# main.net
KiCad netlist of a schematic drawn in Altium Designer
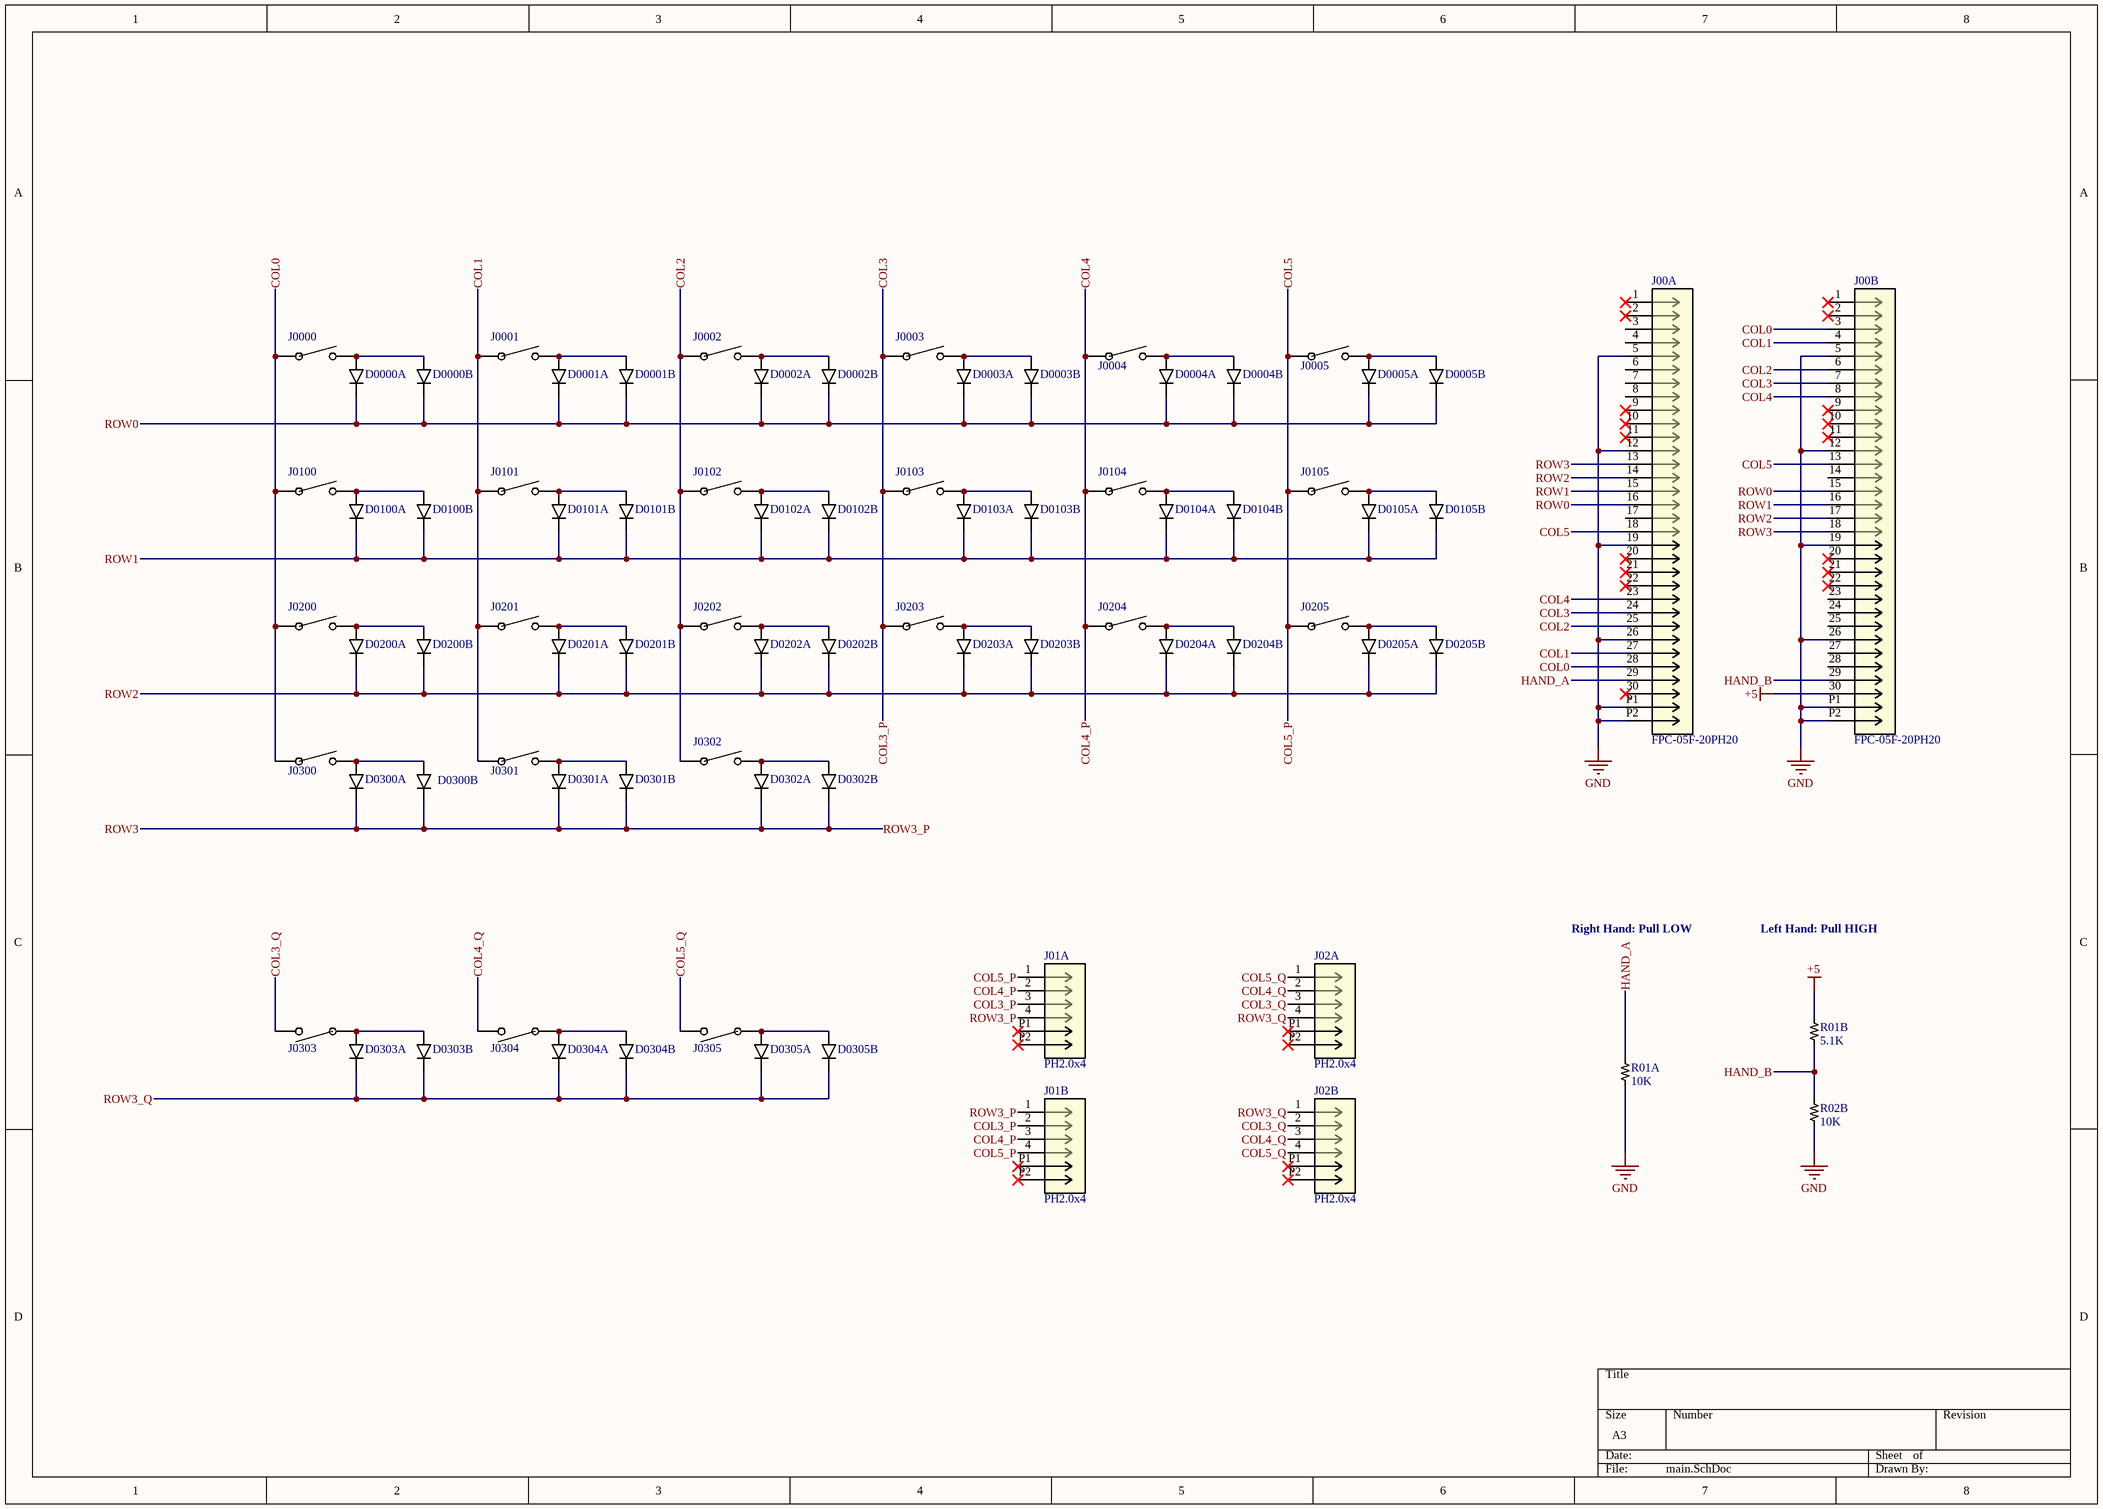
[diagram p0: main.SchDoc]

(export (version "E")
  (design (tool "Eeschema 10.0.6"))
  (components
    (comp (ref "D0000A")
      (value "1N4148W")
      (footprint "SOD123_DIO")
      (description "Small Signal Diode")
      (libsource (lib "Cornix_Library") (part "1N4148W"))
    )
    (comp (ref "D0000B")
      (value "1N4148W")
      (footprint "SOD123_DIO")
      (description "Small Signal Diode")
      (libsource (lib "Cornix_Library") (part "1N4148W"))
    )
    (comp (ref "D0001A")
      (value "1N4148W")
      (footprint "SOD123_DIO")
      (description "Small Signal Diode")
      (libsource (lib "Cornix_Library") (part "1N4148W"))
    )
    (comp (ref "D0001B")
      (value "1N4148W")
      (footprint "SOD123_DIO")
      (description "Small Signal Diode")
      (libsource (lib "Cornix_Library") (part "1N4148W"))
    )
    (comp (ref "D0002A")
      (value "1N4148W")
      (footprint "SOD123_DIO")
      (description "Small Signal Diode")
      (libsource (lib "Cornix_Library") (part "1N4148W"))
    )
    (comp (ref "D0002B")
      (value "1N4148W")
      (footprint "SOD123_DIO")
      (description "Small Signal Diode")
      (libsource (lib "Cornix_Library") (part "1N4148W"))
    )
    (comp (ref "D0003A")
      (value "1N4148W")
      (footprint "SOD123_DIO")
      (description "Small Signal Diode")
      (libsource (lib "Cornix_Library") (part "1N4148W"))
    )
    (comp (ref "D0003B")
      (value "1N4148W")
      (footprint "SOD123_DIO")
      (description "Small Signal Diode")
      (libsource (lib "Cornix_Library") (part "1N4148W"))
    )
    (comp (ref "D0004A")
      (value "1N4148W")
      (footprint "SOD123_DIO")
      (description "Small Signal Diode")
      (libsource (lib "Cornix_Library") (part "1N4148W"))
    )
    (comp (ref "D0004B")
      (value "1N4148W")
      (footprint "SOD123_DIO")
      (description "Small Signal Diode")
      (libsource (lib "Cornix_Library") (part "1N4148W"))
    )
    (comp (ref "D0005A")
      (value "1N4148W")
      (footprint "SOD123_DIO")
      (description "Small Signal Diode")
      (libsource (lib "Cornix_Library") (part "1N4148W"))
    )
    (comp (ref "D0005B")
      (value "1N4148W")
      (footprint "SOD123_DIO")
      (description "Small Signal Diode")
      (libsource (lib "Cornix_Library") (part "1N4148W"))
    )
    (comp (ref "D0100A")
      (value "1N4148W")
      (footprint "SOD123_DIO")
      (description "Small Signal Diode")
      (libsource (lib "Cornix_Library") (part "1N4148W"))
    )
    (comp (ref "D0100B")
      (value "1N4148W")
      (footprint "SOD123_DIO")
      (description "Small Signal Diode")
      (libsource (lib "Cornix_Library") (part "1N4148W"))
    )
    (comp (ref "D0101A")
      (value "1N4148W")
      (footprint "SOD123_DIO")
      (description "Small Signal Diode")
      (libsource (lib "Cornix_Library") (part "1N4148W"))
    )
    (comp (ref "D0101B")
      (value "1N4148W")
      (footprint "SOD123_DIO")
      (description "Small Signal Diode")
      (libsource (lib "Cornix_Library") (part "1N4148W"))
    )
    (comp (ref "D0102A")
      (value "1N4148W")
      (footprint "SOD123_DIO")
      (description "Small Signal Diode")
      (libsource (lib "Cornix_Library") (part "1N4148W"))
    )
    (comp (ref "D0102B")
      (value "1N4148W")
      (footprint "SOD123_DIO")
      (description "Small Signal Diode")
      (libsource (lib "Cornix_Library") (part "1N4148W"))
    )
    (comp (ref "D0103A")
      (value "1N4148W")
      (footprint "SOD123_DIO")
      (description "Small Signal Diode")
      (libsource (lib "Cornix_Library") (part "1N4148W"))
    )
    (comp (ref "D0103B")
      (value "1N4148W")
      (footprint "SOD123_DIO")
      (description "Small Signal Diode")
      (libsource (lib "Cornix_Library") (part "1N4148W"))
    )
    (comp (ref "D0104A")
      (value "1N4148W")
      (footprint "SOD123_DIO")
      (description "Small Signal Diode")
      (libsource (lib "Cornix_Library") (part "1N4148W"))
    )
    (comp (ref "D0104B")
      (value "1N4148W")
      (footprint "SOD123_DIO")
      (description "Small Signal Diode")
      (libsource (lib "Cornix_Library") (part "1N4148W"))
    )
    (comp (ref "D0105A")
      (value "1N4148W")
      (footprint "SOD123_DIO")
      (description "Small Signal Diode")
      (libsource (lib "Cornix_Library") (part "1N4148W"))
    )
    (comp (ref "D0105B")
      (value "1N4148W")
      (footprint "SOD123_DIO")
      (description "Small Signal Diode")
      (libsource (lib "Cornix_Library") (part "1N4148W"))
    )
    (comp (ref "D0200A")
      (value "1N4148W")
      (footprint "SOD123_DIO")
      (description "Small Signal Diode")
      (libsource (lib "Cornix_Library") (part "1N4148W"))
    )
    (comp (ref "D0200B")
      (value "1N4148W")
      (footprint "SOD123_DIO")
      (description "Small Signal Diode")
      (libsource (lib "Cornix_Library") (part "1N4148W"))
    )
    (comp (ref "D0201A")
      (value "1N4148W")
      (footprint "SOD123_DIO")
      (description "Small Signal Diode")
      (libsource (lib "Cornix_Library") (part "1N4148W"))
    )
    (comp (ref "D0201B")
      (value "1N4148W")
      (footprint "SOD123_DIO")
      (description "Small Signal Diode")
      (libsource (lib "Cornix_Library") (part "1N4148W"))
    )
    (comp (ref "D0202A")
      (value "1N4148W")
      (footprint "SOD123_DIO")
      (description "Small Signal Diode")
      (libsource (lib "Cornix_Library") (part "1N4148W"))
    )
    (comp (ref "D0202B")
      (value "1N4148W")
      (footprint "SOD123_DIO")
      (description "Small Signal Diode")
      (libsource (lib "Cornix_Library") (part "1N4148W"))
    )
    (comp (ref "D0203A")
      (value "1N4148W")
      (footprint "SOD123_DIO")
      (description "Small Signal Diode")
      (libsource (lib "Cornix_Library") (part "1N4148W"))
    )
    (comp (ref "D0203B")
      (value "1N4148W")
      (footprint "SOD123_DIO")
      (description "Small Signal Diode")
      (libsource (lib "Cornix_Library") (part "1N4148W"))
    )
    (comp (ref "D0204A")
      (value "1N4148W")
      (footprint "SOD123_DIO")
      (description "Small Signal Diode")
      (libsource (lib "Cornix_Library") (part "1N4148W"))
    )
    (comp (ref "D0204B")
      (value "1N4148W")
      (footprint "SOD123_DIO")
      (description "Small Signal Diode")
      (libsource (lib "Cornix_Library") (part "1N4148W"))
    )
    (comp (ref "D0205A")
      (value "1N4148W")
      (footprint "SOD123_DIO")
      (description "Small Signal Diode")
      (libsource (lib "Cornix_Library") (part "1N4148W"))
    )
    (comp (ref "D0205B")
      (value "1N4148W")
      (footprint "SOD123_DIO")
      (description "Small Signal Diode")
      (libsource (lib "Cornix_Library") (part "1N4148W"))
    )
    (comp (ref "D0300A")
      (value "1N4148W")
      (footprint "SOD123_DIO")
      (description "Small Signal Diode")
      (libsource (lib "Cornix_Library") (part "1N4148W"))
    )
    (comp (ref "D0300B")
      (value "1N4148W")
      (footprint "SOD123_DIO")
      (description "Small Signal Diode")
      (libsource (lib "Cornix_Library") (part "1N4148W"))
    )
    (comp (ref "D0301A")
      (value "1N4148W")
      (footprint "SOD123_DIO")
      (description "Small Signal Diode")
      (libsource (lib "Cornix_Library") (part "1N4148W"))
    )
    (comp (ref "D0301B")
      (value "1N4148W")
      (footprint "SOD123_DIO")
      (description "Small Signal Diode")
      (libsource (lib "Cornix_Library") (part "1N4148W"))
    )
    (comp (ref "D0302A")
      (value "1N4148W")
      (footprint "SOD123_DIO")
      (description "Small Signal Diode")
      (libsource (lib "Cornix_Library") (part "1N4148W"))
    )
    (comp (ref "D0302B")
      (value "1N4148W")
      (footprint "SOD123_DIO")
      (description "Small Signal Diode")
      (libsource (lib "Cornix_Library") (part "1N4148W"))
    )
    (comp (ref "D0303A")
      (value "1N4148W")
      (footprint "SOD123_DIO")
      (description "Small Signal Diode")
      (libsource (lib "Cornix_Library") (part "1N4148W"))
    )
    (comp (ref "D0303B")
      (value "1N4148W")
      (footprint "SOD123_DIO")
      (description "Small Signal Diode")
      (libsource (lib "Cornix_Library") (part "1N4148W"))
    )
    (comp (ref "D0304A")
      (value "1N4148W")
      (footprint "SOD123_DIO")
      (description "Small Signal Diode")
      (libsource (lib "Cornix_Library") (part "1N4148W"))
    )
    (comp (ref "D0304B")
      (value "1N4148W")
      (footprint "SOD123_DIO")
      (description "Small Signal Diode")
      (libsource (lib "Cornix_Library") (part "1N4148W"))
    )
    (comp (ref "D0305A")
      (value "1N4148W")
      (footprint "SOD123_DIO")
      (description "Small Signal Diode")
      (libsource (lib "Cornix_Library") (part "1N4148W"))
    )
    (comp (ref "D0305B")
      (value "1N4148W")
      (footprint "SOD123_DIO")
      (description "Small Signal Diode")
      (libsource (lib "Cornix_Library") (part "1N4148W"))
    )
    (comp (ref "J0000")
      (value "Gateron_V2")
      (footprint "Gateron_V2")
      (description "Gateron hotswap socket V2.0")
      (libsource (lib "Cornix_Library") (part "Gateron_V2"))
    )
    (comp (ref "J00A")
      (value "FPC-05F-20PH20")
      (footprint "FPC-05F-30PH20")
      (description "30 Pin 0.5 Pitch FPC connector")
      (libsource (lib "Cornix_Library") (part "FPC-05F-30PH20"))
    )
    (comp (ref "J00B")
      (value "FPC-05F-20PH20")
      (footprint "FPC-05F-30PH20")
      (description "30 Pin 0.5 Pitch FPC connector")
      (libsource (lib "Cornix_Library") (part "FPC-05F-30PH20"))
    )
    (comp (ref "J0001")
      (value "Gateron_V2")
      (footprint "Gateron_V2")
      (description "Gateron hotswap socket V2.0")
      (libsource (lib "Cornix_Library") (part "Gateron_V2"))
    )
    (comp (ref "J01A")
      (value "PH2.0x4")
      (footprint "PH2.0x4P")
      (description "PH2.0 4Pin Connector (vertical SMD)")
      (libsource (lib "Cornix_Library") (part "PH2.0x4"))
    )
    (comp (ref "J01B")
      (value "PH2.0x4")
      (footprint "PH2.0x4P")
      (description "PH2.0 4Pin Connector (vertical SMD)")
      (libsource (lib "Cornix_Library") (part "PH2.0x4"))
    )
    (comp (ref "J0002")
      (value "Gateron_V2")
      (footprint "Gateron_V2")
      (description "Gateron hotswap socket V2.0")
      (libsource (lib "Cornix_Library") (part "Gateron_V2"))
    )
    (comp (ref "J02A")
      (value "PH2.0x4")
      (footprint "PH2.0x4P")
      (description "PH2.0 4Pin Connector (vertical SMD)")
      (libsource (lib "Cornix_Library") (part "PH2.0x4"))
    )
    (comp (ref "J02B")
      (value "PH2.0x4")
      (footprint "PH2.0x4P")
      (description "PH2.0 4Pin Connector (vertical SMD)")
      (libsource (lib "Cornix_Library") (part "PH2.0x4"))
    )
    (comp (ref "J0003")
      (value "Gateron_V2")
      (footprint "Gateron_V2")
      (description "Gateron hotswap socket V2.0")
      (libsource (lib "Cornix_Library") (part "Gateron_V2"))
    )
    (comp (ref "J0004")
      (value "Gateron_V2")
      (footprint "Gateron_V2")
      (description "Gateron hotswap socket V2.0")
      (libsource (lib "") (part "Gateron_V2_1"))
    )
    (comp (ref "J0005")
      (value "Gateron_V2")
      (footprint "Gateron_V2")
      (description "Gateron hotswap socket V2.0")
      (libsource (lib "") (part "Gateron_V2_1"))
    )
    (comp (ref "J0100")
      (value "Gateron_V2")
      (footprint "Gateron_V2")
      (description "Gateron hotswap socket V2.0")
      (libsource (lib "Cornix_Library") (part "Gateron_V2"))
    )
    (comp (ref "J0101")
      (value "Gateron_V2")
      (footprint "Gateron_V2")
      (description "Gateron hotswap socket V2.0")
      (libsource (lib "Cornix_Library") (part "Gateron_V2"))
    )
    (comp (ref "J0102")
      (value "Gateron_V2")
      (footprint "Gateron_V2")
      (description "Gateron hotswap socket V2.0")
      (libsource (lib "Cornix_Library") (part "Gateron_V2"))
    )
    (comp (ref "J0103")
      (value "Gateron_V2")
      (footprint "Gateron_V2")
      (description "Gateron hotswap socket V2.0")
      (libsource (lib "Cornix_Library") (part "Gateron_V2"))
    )
    (comp (ref "J0104")
      (value "Gateron_V2")
      (footprint "Gateron_V2")
      (description "Gateron hotswap socket V2.0")
      (libsource (lib "Cornix_Library") (part "Gateron_V2"))
    )
    (comp (ref "J0105")
      (value "Gateron_V2")
      (footprint "Gateron_V2")
      (description "Gateron hotswap socket V2.0")
      (libsource (lib "Cornix_Library") (part "Gateron_V2"))
    )
    (comp (ref "J0200")
      (value "Gateron_V2")
      (footprint "Gateron_V2")
      (description "Gateron hotswap socket V2.0")
      (libsource (lib "Cornix_Library") (part "Gateron_V2"))
    )
    (comp (ref "J0201")
      (value "Gateron_V2")
      (footprint "Gateron_V2")
      (description "Gateron hotswap socket V2.0")
      (libsource (lib "Cornix_Library") (part "Gateron_V2"))
    )
    (comp (ref "J0202")
      (value "Gateron_V2")
      (footprint "Gateron_V2")
      (description "Gateron hotswap socket V2.0")
      (libsource (lib "Cornix_Library") (part "Gateron_V2"))
    )
    (comp (ref "J0203")
      (value "Gateron_V2")
      (footprint "Gateron_V2")
      (description "Gateron hotswap socket V2.0")
      (libsource (lib "Cornix_Library") (part "Gateron_V2"))
    )
    (comp (ref "J0204")
      (value "Gateron_V2")
      (footprint "Gateron_V2")
      (description "Gateron hotswap socket V2.0")
      (libsource (lib "Cornix_Library") (part "Gateron_V2"))
    )
    (comp (ref "J0205")
      (value "Gateron_V2")
      (footprint "Gateron_V2")
      (description "Gateron hotswap socket V2.0")
      (libsource (lib "Cornix_Library") (part "Gateron_V2"))
    )
    (comp (ref "J0300")
      (value "Gateron_V2")
      (footprint "Gateron_V2")
      (description "Gateron hotswap socket V2.0")
      (libsource (lib "") (part "Gateron_V2_1"))
    )
    (comp (ref "J0301")
      (value "Gateron_V2")
      (footprint "Gateron_V2")
      (description "Gateron hotswap socket V2.0")
      (libsource (lib "") (part "Gateron_V2_1"))
    )
    (comp (ref "J0302")
      (value "Gateron_V2")
      (footprint "Gateron_V2")
      (description "Gateron hotswap socket V2.0")
      (libsource (lib "Cornix_Library") (part "Gateron_V2"))
    )
    (comp (ref "J0303")
      (value "Gateron_V2")
      (footprint "Gateron_V2")
      (description "Gateron hotswap socket V2.0")
      (libsource (lib "") (part "Gateron_V2_1"))
    )
    (comp (ref "J0304")
      (value "Gateron_V2")
      (footprint "Gateron_V2")
      (description "Gateron hotswap socket V2.0")
      (libsource (lib "") (part "Gateron_V2_1"))
    )
    (comp (ref "J0305")
      (value "Gateron_V2")
      (footprint "Gateron_V2")
      (description "Gateron hotswap socket V2.0")
      (libsource (lib "") (part "Gateron_V2_1"))
    )
    (comp (ref "R01A")
      (value "10K")
      (footprint "RES0402_CPF_TYCO_TYC")
      (description "CPF 0402 RL")
      (fields
        (field (name "MANUFACTURER_PART_NUMBER") "CPF0402B33RE1")
        (field (name "COPYRIGHT") "Copyright (C) 2025 Ultra Librarian. All rights reserved.")
      )
      (libsource (lib "Cornix_Library") (part "R0402"))
    )
    (comp (ref "R01B")
      (value "5.1K")
      (footprint "RES0402_CPF_TYCO_TYC")
      (description "CPF 0402 RL")
      (fields
        (field (name "MANUFACTURER_PART_NUMBER") "CPF0402B33RE1")
        (field (name "COPYRIGHT") "Copyright (C) 2025 Ultra Librarian. All rights reserved.")
      )
      (libsource (lib "Cornix_Library") (part "R0402"))
    )
    (comp (ref "R02B")
      (value "10K")
      (footprint "RES0402_CPF_TYCO_TYC")
      (description "CPF 0402 RL")
      (fields
        (field (name "MANUFACTURER_PART_NUMBER") "CPF0402B33RE1")
        (field (name "COPYRIGHT") "Copyright (C) 2025 Ultra Librarian. All rights reserved.")
      )
      (libsource (lib "Cornix_Library") (part "R0402"))
    )
  )
  (nets
    (net (code "1") (name "+5") (class "Default")
      (node (ref "J00B") (pin "30") (pinfunction "30_30") (pintype "passive"))
      (node (ref "R01B") (pin "1") (pinfunction "1_1") (pintype "passive"))
    )
    (net (code "2") (name "/COL0") (class "Default")
      (node (ref "J0000") (pin "1") (pinfunction "1_1") (pintype "passive"))
      (node (ref "J00A") (pin "28") (pinfunction "28_28") (pintype "passive"))
      (node (ref "J00B") (pin "3") (pinfunction "3_3") (pintype "passive"))
      (node (ref "J0100") (pin "1") (pinfunction "1_1") (pintype "passive"))
      (node (ref "J0200") (pin "1") (pinfunction "1_1") (pintype "passive"))
      (node (ref "J0300") (pin "1") (pinfunction "1_1") (pintype "passive"))
    )
    (net (code "3") (name "/COL1") (class "Default")
      (node (ref "J0001") (pin "1") (pinfunction "1_1") (pintype "passive"))
      (node (ref "J00A") (pin "27") (pinfunction "27_27") (pintype "passive"))
      (node (ref "J00B") (pin "4") (pinfunction "4_4") (pintype "passive"))
      (node (ref "J0101") (pin "1") (pinfunction "1_1") (pintype "passive"))
      (node (ref "J0201") (pin "1") (pinfunction "1_1") (pintype "passive"))
      (node (ref "J0301") (pin "1") (pinfunction "1_1") (pintype "passive"))
    )
    (net (code "4") (name "/COL2") (class "Default")
      (node (ref "J0002") (pin "1") (pinfunction "1_1") (pintype "passive"))
      (node (ref "J00A") (pin "25") (pinfunction "25_25") (pintype "passive"))
      (node (ref "J00B") (pin "6") (pinfunction "6_6") (pintype "passive"))
      (node (ref "J0102") (pin "1") (pinfunction "1_1") (pintype "passive"))
      (node (ref "J0202") (pin "1") (pinfunction "1_1") (pintype "passive"))
      (node (ref "J0302") (pin "1") (pinfunction "1_1") (pintype "passive"))
    )
    (net (code "5") (name "/COL3") (class "Default")
      (node (ref "J0003") (pin "1") (pinfunction "1_1") (pintype "passive"))
      (node (ref "J00A") (pin "24") (pinfunction "24_24") (pintype "passive"))
      (node (ref "J00B") (pin "7") (pinfunction "7_7") (pintype "passive"))
      (node (ref "J0103") (pin "1") (pinfunction "1_1") (pintype "passive"))
      (node (ref "J01A") (pin "3") (pinfunction "3_3") (pintype "passive"))
      (node (ref "J01B") (pin "2") (pinfunction "2_2") (pintype "passive"))
      (node (ref "J0203") (pin "1") (pinfunction "1_1") (pintype "passive"))
    )
    (net (code "6") (name "/COL3_Q") (class "Default")
      (node (ref "J02A") (pin "3") (pinfunction "3_3") (pintype "passive"))
      (node (ref "J02B") (pin "2") (pinfunction "2_2") (pintype "passive"))
      (node (ref "J0303") (pin "2") (pinfunction "2_2") (pintype "passive"))
    )
    (net (code "7") (name "/COL4") (class "Default")
      (node (ref "J0004") (pin "1") (pinfunction "1_1") (pintype "passive"))
      (node (ref "J00A") (pin "23") (pinfunction "23_23") (pintype "passive"))
      (node (ref "J00B") (pin "8") (pinfunction "8_8") (pintype "passive"))
      (node (ref "J0104") (pin "1") (pinfunction "1_1") (pintype "passive"))
      (node (ref "J01A") (pin "2") (pinfunction "2_2") (pintype "passive"))
      (node (ref "J01B") (pin "3") (pinfunction "3_3") (pintype "passive"))
      (node (ref "J0204") (pin "1") (pinfunction "1_1") (pintype "passive"))
    )
    (net (code "8") (name "/COL4_Q") (class "Default")
      (node (ref "J02A") (pin "2") (pinfunction "2_2") (pintype "passive"))
      (node (ref "J02B") (pin "3") (pinfunction "3_3") (pintype "passive"))
      (node (ref "J0304") (pin "2") (pinfunction "2_2") (pintype "passive"))
    )
    (net (code "9") (name "/COL5") (class "Default")
      (node (ref "J0005") (pin "1") (pinfunction "1_1") (pintype "passive"))
      (node (ref "J00A") (pin "18") (pinfunction "18_18") (pintype "passive"))
      (node (ref "J00B") (pin "13") (pinfunction "13_13") (pintype "passive"))
      (node (ref "J0105") (pin "1") (pinfunction "1_1") (pintype "passive"))
      (node (ref "J01A") (pin "1") (pinfunction "1_1") (pintype "passive"))
      (node (ref "J01B") (pin "4") (pinfunction "4_4") (pintype "passive"))
      (node (ref "J0205") (pin "1") (pinfunction "1_1") (pintype "passive"))
    )
    (net (code "10") (name "/COL5_Q") (class "Default")
      (node (ref "J02A") (pin "1") (pinfunction "1_1") (pintype "passive"))
      (node (ref "J02B") (pin "4") (pinfunction "4_4") (pintype "passive"))
      (node (ref "J0305") (pin "2") (pinfunction "2_2") (pintype "passive"))
    )
    (net (code "11") (name "/HAND_A") (class "Default")
      (node (ref "J00A") (pin "29") (pinfunction "29_29") (pintype "passive"))
      (node (ref "R01A") (pin "1") (pinfunction "1_1") (pintype "passive"))
    )
    (net (code "12") (name "/HAND_B") (class "Default")
      (node (ref "J00B") (pin "29") (pinfunction "29_29") (pintype "passive"))
      (node (ref "R01B") (pin "2") (pinfunction "2_2") (pintype "passive"))
      (node (ref "R02B") (pin "1") (pinfunction "1_1") (pintype "passive"))
    )
    (net (code "13") (name "/ROW0") (class "Default")
      (node (ref "D0000A") (pin "K") (pinfunction "K_K") (pintype "passive"))
      (node (ref "D0000B") (pin "K") (pinfunction "K_K") (pintype "passive"))
      (node (ref "D0001A") (pin "K") (pinfunction "K_K") (pintype "passive"))
      (node (ref "D0001B") (pin "K") (pinfunction "K_K") (pintype "passive"))
      (node (ref "D0002A") (pin "K") (pinfunction "K_K") (pintype "passive"))
      (node (ref "D0002B") (pin "K") (pinfunction "K_K") (pintype "passive"))
      (node (ref "D0003A") (pin "K") (pinfunction "K_K") (pintype "passive"))
      (node (ref "D0003B") (pin "K") (pinfunction "K_K") (pintype "passive"))
      (node (ref "D0004A") (pin "K") (pinfunction "K_K") (pintype "passive"))
      (node (ref "D0004B") (pin "K") (pinfunction "K_K") (pintype "passive"))
      (node (ref "D0005A") (pin "K") (pinfunction "K_K") (pintype "passive"))
      (node (ref "D0005B") (pin "K") (pinfunction "K_K") (pintype "passive"))
      (node (ref "J00A") (pin "16") (pinfunction "16_16") (pintype "passive"))
      (node (ref "J00B") (pin "15") (pinfunction "15_15") (pintype "passive"))
    )
    (net (code "14") (name "/ROW1") (class "Default")
      (node (ref "D0100A") (pin "K") (pinfunction "K_K") (pintype "passive"))
      (node (ref "D0100B") (pin "K") (pinfunction "K_K") (pintype "passive"))
      (node (ref "D0101A") (pin "K") (pinfunction "K_K") (pintype "passive"))
      (node (ref "D0101B") (pin "K") (pinfunction "K_K") (pintype "passive"))
      (node (ref "D0102A") (pin "K") (pinfunction "K_K") (pintype "passive"))
      (node (ref "D0102B") (pin "K") (pinfunction "K_K") (pintype "passive"))
      (node (ref "D0103A") (pin "K") (pinfunction "K_K") (pintype "passive"))
      (node (ref "D0103B") (pin "K") (pinfunction "K_K") (pintype "passive"))
      (node (ref "D0104A") (pin "K") (pinfunction "K_K") (pintype "passive"))
      (node (ref "D0104B") (pin "K") (pinfunction "K_K") (pintype "passive"))
      (node (ref "D0105A") (pin "K") (pinfunction "K_K") (pintype "passive"))
      (node (ref "D0105B") (pin "K") (pinfunction "K_K") (pintype "passive"))
      (node (ref "J00A") (pin "15") (pinfunction "15_15") (pintype "passive"))
      (node (ref "J00B") (pin "16") (pinfunction "16_16") (pintype "passive"))
    )
    (net (code "15") (name "/ROW2") (class "Default")
      (node (ref "D0200A") (pin "K") (pinfunction "K_K") (pintype "passive"))
      (node (ref "D0200B") (pin "K") (pinfunction "K_K") (pintype "passive"))
      (node (ref "D0201A") (pin "K") (pinfunction "K_K") (pintype "passive"))
      (node (ref "D0201B") (pin "K") (pinfunction "K_K") (pintype "passive"))
      (node (ref "D0202A") (pin "K") (pinfunction "K_K") (pintype "passive"))
      (node (ref "D0202B") (pin "K") (pinfunction "K_K") (pintype "passive"))
      (node (ref "D0203A") (pin "K") (pinfunction "K_K") (pintype "passive"))
      (node (ref "D0203B") (pin "K") (pinfunction "K_K") (pintype "passive"))
      (node (ref "D0204A") (pin "K") (pinfunction "K_K") (pintype "passive"))
      (node (ref "D0204B") (pin "K") (pinfunction "K_K") (pintype "passive"))
      (node (ref "D0205A") (pin "K") (pinfunction "K_K") (pintype "passive"))
      (node (ref "D0205B") (pin "K") (pinfunction "K_K") (pintype "passive"))
      (node (ref "J00A") (pin "14") (pinfunction "14_14") (pintype "passive"))
      (node (ref "J00B") (pin "17") (pinfunction "17_17") (pintype "passive"))
    )
    (net (code "16") (name "/ROW3") (class "Default")
      (node (ref "D0300A") (pin "K") (pinfunction "K_K") (pintype "passive"))
      (node (ref "D0300B") (pin "K") (pinfunction "K_K") (pintype "passive"))
      (node (ref "D0301A") (pin "K") (pinfunction "K_K") (pintype "passive"))
      (node (ref "D0301B") (pin "K") (pinfunction "K_K") (pintype "passive"))
      (node (ref "D0302A") (pin "K") (pinfunction "K_K") (pintype "passive"))
      (node (ref "D0302B") (pin "K") (pinfunction "K_K") (pintype "passive"))
      (node (ref "J00A") (pin "13") (pinfunction "13_13") (pintype "passive"))
      (node (ref "J00B") (pin "18") (pinfunction "18_18") (pintype "passive"))
      (node (ref "J01A") (pin "4") (pinfunction "4_4") (pintype "passive"))
      (node (ref "J01B") (pin "1") (pinfunction "1_1") (pintype "passive"))
    )
    (net (code "17") (name "/ROW3_Q") (class "Default")
      (node (ref "D0303A") (pin "K") (pinfunction "K_K") (pintype "passive"))
      (node (ref "D0303B") (pin "K") (pinfunction "K_K") (pintype "passive"))
      (node (ref "D0304A") (pin "K") (pinfunction "K_K") (pintype "passive"))
      (node (ref "D0304B") (pin "K") (pinfunction "K_K") (pintype "passive"))
      (node (ref "D0305A") (pin "K") (pinfunction "K_K") (pintype "passive"))
      (node (ref "D0305B") (pin "K") (pinfunction "K_K") (pintype "passive"))
      (node (ref "J02A") (pin "4") (pinfunction "4_4") (pintype "passive"))
      (node (ref "J02B") (pin "1") (pinfunction "1_1") (pintype "passive"))
    )
    (net (code "18") (name "GND") (class "Default")
      (node (ref "J00A") (pin "12") (pinfunction "12_12") (pintype "passive"))
      (node (ref "J00A") (pin "19") (pinfunction "19_19") (pintype "passive"))
      (node (ref "J00A") (pin "26") (pinfunction "26_26") (pintype "passive"))
      (node (ref "J00A") (pin "5") (pinfunction "5_5") (pintype "passive"))
      (node (ref "J00A") (pin "P1") (pinfunction "P1_P1") (pintype "passive"))
      (node (ref "J00A") (pin "P2") (pinfunction "P2_P2") (pintype "passive"))
      (node (ref "J00B") (pin "12") (pinfunction "12_12") (pintype "passive"))
      (node (ref "J00B") (pin "19") (pinfunction "19_19") (pintype "passive"))
      (node (ref "J00B") (pin "26") (pinfunction "26_26") (pintype "passive"))
      (node (ref "J00B") (pin "5") (pinfunction "5_5") (pintype "passive"))
      (node (ref "J00B") (pin "P1") (pinfunction "P1_P1") (pintype "passive"))
      (node (ref "J00B") (pin "P2") (pinfunction "P2_P2") (pintype "passive"))
      (node (ref "R01A") (pin "2") (pinfunction "2_2") (pintype "passive"))
      (node (ref "R02B") (pin "2") (pinfunction "2_2") (pintype "passive"))
    )
    (net (code "19") (name "Net-(D0000A-PadA)") (class "Default")
      (node (ref "D0000A") (pin "A") (pinfunction "A_A") (pintype "passive"))
      (node (ref "D0000B") (pin "A") (pinfunction "A_A") (pintype "passive"))
      (node (ref "J0000") (pin "2") (pinfunction "2_2") (pintype "passive"))
    )
    (net (code "20") (name "Net-(D0001A-PadA)") (class "Default")
      (node (ref "D0001A") (pin "A") (pinfunction "A_A") (pintype "passive"))
      (node (ref "D0001B") (pin "A") (pinfunction "A_A") (pintype "passive"))
      (node (ref "J0001") (pin "2") (pinfunction "2_2") (pintype "passive"))
    )
    (net (code "21") (name "Net-(D0002A-PadA)") (class "Default")
      (node (ref "D0002A") (pin "A") (pinfunction "A_A") (pintype "passive"))
      (node (ref "D0002B") (pin "A") (pinfunction "A_A") (pintype "passive"))
      (node (ref "J0002") (pin "2") (pinfunction "2_2") (pintype "passive"))
    )
    (net (code "22") (name "Net-(D0003A-PadA)") (class "Default")
      (node (ref "D0003A") (pin "A") (pinfunction "A_A") (pintype "passive"))
      (node (ref "D0003B") (pin "A") (pinfunction "A_A") (pintype "passive"))
      (node (ref "J0003") (pin "2") (pinfunction "2_2") (pintype "passive"))
    )
    (net (code "23") (name "Net-(D0004A-PadA)") (class "Default")
      (node (ref "D0004A") (pin "A") (pinfunction "A_A") (pintype "passive"))
      (node (ref "D0004B") (pin "A") (pinfunction "A_A") (pintype "passive"))
      (node (ref "J0004") (pin "2") (pinfunction "2_2") (pintype "passive"))
    )
    (net (code "24") (name "Net-(D0005A-PadA)") (class "Default")
      (node (ref "D0005A") (pin "A") (pinfunction "A_A") (pintype "passive"))
      (node (ref "D0005B") (pin "A") (pinfunction "A_A") (pintype "passive"))
      (node (ref "J0005") (pin "2") (pinfunction "2_2") (pintype "passive"))
    )
    (net (code "25") (name "Net-(D0100A-PadA)") (class "Default")
      (node (ref "D0100A") (pin "A") (pinfunction "A_A") (pintype "passive"))
      (node (ref "D0100B") (pin "A") (pinfunction "A_A") (pintype "passive"))
      (node (ref "J0100") (pin "2") (pinfunction "2_2") (pintype "passive"))
    )
    (net (code "26") (name "Net-(D0101A-PadA)") (class "Default")
      (node (ref "D0101A") (pin "A") (pinfunction "A_A") (pintype "passive"))
      (node (ref "D0101B") (pin "A") (pinfunction "A_A") (pintype "passive"))
      (node (ref "J0101") (pin "2") (pinfunction "2_2") (pintype "passive"))
    )
    (net (code "27") (name "Net-(D0102A-PadA)") (class "Default")
      (node (ref "D0102A") (pin "A") (pinfunction "A_A") (pintype "passive"))
      (node (ref "D0102B") (pin "A") (pinfunction "A_A") (pintype "passive"))
      (node (ref "J0102") (pin "2") (pinfunction "2_2") (pintype "passive"))
    )
    (net (code "28") (name "Net-(D0103A-PadA)") (class "Default")
      (node (ref "D0103A") (pin "A") (pinfunction "A_A") (pintype "passive"))
      (node (ref "D0103B") (pin "A") (pinfunction "A_A") (pintype "passive"))
      (node (ref "J0103") (pin "2") (pinfunction "2_2") (pintype "passive"))
    )
    (net (code "29") (name "Net-(D0104A-PadA)") (class "Default")
      (node (ref "D0104A") (pin "A") (pinfunction "A_A") (pintype "passive"))
      (node (ref "D0104B") (pin "A") (pinfunction "A_A") (pintype "passive"))
      (node (ref "J0104") (pin "2") (pinfunction "2_2") (pintype "passive"))
    )
    (net (code "30") (name "Net-(D0105A-PadA)") (class "Default")
      (node (ref "D0105A") (pin "A") (pinfunction "A_A") (pintype "passive"))
      (node (ref "D0105B") (pin "A") (pinfunction "A_A") (pintype "passive"))
      (node (ref "J0105") (pin "2") (pinfunction "2_2") (pintype "passive"))
    )
    (net (code "31") (name "Net-(D0200A-PadA)") (class "Default")
      (node (ref "D0200A") (pin "A") (pinfunction "A_A") (pintype "passive"))
      (node (ref "D0200B") (pin "A") (pinfunction "A_A") (pintype "passive"))
      (node (ref "J0200") (pin "2") (pinfunction "2_2") (pintype "passive"))
    )
    (net (code "32") (name "Net-(D0201A-PadA)") (class "Default")
      (node (ref "D0201A") (pin "A") (pinfunction "A_A") (pintype "passive"))
      (node (ref "D0201B") (pin "A") (pinfunction "A_A") (pintype "passive"))
      (node (ref "J0201") (pin "2") (pinfunction "2_2") (pintype "passive"))
    )
    (net (code "33") (name "Net-(D0202A-PadA)") (class "Default")
      (node (ref "D0202A") (pin "A") (pinfunction "A_A") (pintype "passive"))
      (node (ref "D0202B") (pin "A") (pinfunction "A_A") (pintype "passive"))
      (node (ref "J0202") (pin "2") (pinfunction "2_2") (pintype "passive"))
    )
    (net (code "34") (name "Net-(D0203A-PadA)") (class "Default")
      (node (ref "D0203A") (pin "A") (pinfunction "A_A") (pintype "passive"))
      (node (ref "D0203B") (pin "A") (pinfunction "A_A") (pintype "passive"))
      (node (ref "J0203") (pin "2") (pinfunction "2_2") (pintype "passive"))
    )
    (net (code "35") (name "Net-(D0204A-PadA)") (class "Default")
      (node (ref "D0204A") (pin "A") (pinfunction "A_A") (pintype "passive"))
      (node (ref "D0204B") (pin "A") (pinfunction "A_A") (pintype "passive"))
      (node (ref "J0204") (pin "2") (pinfunction "2_2") (pintype "passive"))
    )
    (net (code "36") (name "Net-(D0205A-PadA)") (class "Default")
      (node (ref "D0205A") (pin "A") (pinfunction "A_A") (pintype "passive"))
      (node (ref "D0205B") (pin "A") (pinfunction "A_A") (pintype "passive"))
      (node (ref "J0205") (pin "2") (pinfunction "2_2") (pintype "passive"))
    )
    (net (code "37") (name "Net-(D0300A-PadA)") (class "Default")
      (node (ref "D0300A") (pin "A") (pinfunction "A_A") (pintype "passive"))
      (node (ref "D0300B") (pin "A") (pinfunction "A_A") (pintype "passive"))
      (node (ref "J0300") (pin "2") (pinfunction "2_2") (pintype "passive"))
    )
    (net (code "38") (name "Net-(D0301A-PadA)") (class "Default")
      (node (ref "D0301A") (pin "A") (pinfunction "A_A") (pintype "passive"))
      (node (ref "D0301B") (pin "A") (pinfunction "A_A") (pintype "passive"))
      (node (ref "J0301") (pin "2") (pinfunction "2_2") (pintype "passive"))
    )
    (net (code "39") (name "Net-(D0302A-PadA)") (class "Default")
      (node (ref "D0302A") (pin "A") (pinfunction "A_A") (pintype "passive"))
      (node (ref "D0302B") (pin "A") (pinfunction "A_A") (pintype "passive"))
      (node (ref "J0302") (pin "2") (pinfunction "2_2") (pintype "passive"))
    )
    (net (code "40") (name "Net-(D0303A-PadA)") (class "Default")
      (node (ref "D0303A") (pin "A") (pinfunction "A_A") (pintype "passive"))
      (node (ref "D0303B") (pin "A") (pinfunction "A_A") (pintype "passive"))
      (node (ref "J0303") (pin "1") (pinfunction "1_1") (pintype "passive"))
    )
    (net (code "41") (name "Net-(D0304A-PadA)") (class "Default")
      (node (ref "D0304A") (pin "A") (pinfunction "A_A") (pintype "passive"))
      (node (ref "D0304B") (pin "A") (pinfunction "A_A") (pintype "passive"))
      (node (ref "J0304") (pin "1") (pinfunction "1_1") (pintype "passive"))
    )
    (net (code "42") (name "Net-(D0305A-PadA)") (class "Default")
      (node (ref "D0305A") (pin "A") (pinfunction "A_A") (pintype "passive"))
      (node (ref "D0305B") (pin "A") (pinfunction "A_A") (pintype "passive"))
      (node (ref "J0305") (pin "1") (pinfunction "1_1") (pintype "passive"))
    )
    (net (code "43") (name "unconnected-(J00A-Pad1)") (class "Default")
      (node (ref "J00A") (pin "1") (pinfunction "1_1") (pintype "passive+no_connect"))
    )
    (net (code "44") (name "unconnected-(J00A-Pad2)") (class "Default")
      (node (ref "J00A") (pin "2") (pinfunction "2_2") (pintype "passive+no_connect"))
    )
    (net (code "45") (name "unconnected-(J00A-Pad3)") (class "Default")
      (node (ref "J00A") (pin "3") (pinfunction "3_3") (pintype "passive"))
    )
    (net (code "46") (name "unconnected-(J00A-Pad4)") (class "Default")
      (node (ref "J00A") (pin "4") (pinfunction "4_4") (pintype "passive"))
    )
    (net (code "47") (name "unconnected-(J00A-Pad6)") (class "Default")
      (node (ref "J00A") (pin "6") (pinfunction "6_6") (pintype "passive"))
    )
    (net (code "48") (name "unconnected-(J00A-Pad7)") (class "Default")
      (node (ref "J00A") (pin "7") (pinfunction "7_7") (pintype "passive"))
    )
    (net (code "49") (name "unconnected-(J00A-Pad8)") (class "Default")
      (node (ref "J00A") (pin "8") (pinfunction "8_8") (pintype "passive"))
    )
    (net (code "50") (name "unconnected-(J00A-Pad9)") (class "Default")
      (node (ref "J00A") (pin "9") (pinfunction "9_9") (pintype "passive+no_connect"))
    )
    (net (code "51") (name "unconnected-(J00A-Pad10)") (class "Default")
      (node (ref "J00A") (pin "10") (pinfunction "10_10") (pintype "passive+no_connect"))
    )
    (net (code "52") (name "unconnected-(J00A-Pad11)") (class "Default")
      (node (ref "J00A") (pin "11") (pinfunction "11_11") (pintype "passive+no_connect"))
    )
    (net (code "53") (name "unconnected-(J00A-Pad17)") (class "Default")
      (node (ref "J00A") (pin "17") (pinfunction "17_17") (pintype "passive"))
    )
    (net (code "54") (name "unconnected-(J00A-Pad20)") (class "Default")
      (node (ref "J00A") (pin "20") (pinfunction "20_20") (pintype "passive+no_connect"))
    )
    (net (code "55") (name "unconnected-(J00A-Pad21)") (class "Default")
      (node (ref "J00A") (pin "21") (pinfunction "21_21") (pintype "passive+no_connect"))
    )
    (net (code "56") (name "unconnected-(J00A-Pad22)") (class "Default")
      (node (ref "J00A") (pin "22") (pinfunction "22_22") (pintype "passive+no_connect"))
    )
    (net (code "57") (name "unconnected-(J00A-Pad30)") (class "Default")
      (node (ref "J00A") (pin "30") (pinfunction "30_30") (pintype "passive+no_connect"))
    )
    (net (code "58") (name "unconnected-(J00B-Pad1)") (class "Default")
      (node (ref "J00B") (pin "1") (pinfunction "1_1") (pintype "passive+no_connect"))
    )
    (net (code "59") (name "unconnected-(J00B-Pad2)") (class "Default")
      (node (ref "J00B") (pin "2") (pinfunction "2_2") (pintype "passive+no_connect"))
    )
    (net (code "60") (name "unconnected-(J00B-Pad9)") (class "Default")
      (node (ref "J00B") (pin "9") (pinfunction "9_9") (pintype "passive+no_connect"))
    )
    (net (code "61") (name "unconnected-(J00B-Pad10)") (class "Default")
      (node (ref "J00B") (pin "10") (pinfunction "10_10") (pintype "passive+no_connect"))
    )
    (net (code "62") (name "unconnected-(J00B-Pad11)") (class "Default")
      (node (ref "J00B") (pin "11") (pinfunction "11_11") (pintype "passive+no_connect"))
    )
    (net (code "63") (name "unconnected-(J00B-Pad14)") (class "Default")
      (node (ref "J00B") (pin "14") (pinfunction "14_14") (pintype "passive"))
    )
    (net (code "64") (name "unconnected-(J00B-Pad20)") (class "Default")
      (node (ref "J00B") (pin "20") (pinfunction "20_20") (pintype "passive+no_connect"))
    )
    (net (code "65") (name "unconnected-(J00B-Pad21)") (class "Default")
      (node (ref "J00B") (pin "21") (pinfunction "21_21") (pintype "passive+no_connect"))
    )
    (net (code "66") (name "unconnected-(J00B-Pad22)") (class "Default")
      (node (ref "J00B") (pin "22") (pinfunction "22_22") (pintype "passive+no_connect"))
    )
    (net (code "67") (name "unconnected-(J00B-Pad23)") (class "Default")
      (node (ref "J00B") (pin "23") (pinfunction "23_23") (pintype "passive"))
    )
    (net (code "68") (name "unconnected-(J00B-Pad24)") (class "Default")
      (node (ref "J00B") (pin "24") (pinfunction "24_24") (pintype "passive"))
    )
    (net (code "69") (name "unconnected-(J00B-Pad25)") (class "Default")
      (node (ref "J00B") (pin "25") (pinfunction "25_25") (pintype "passive"))
    )
    (net (code "70") (name "unconnected-(J00B-Pad27)") (class "Default")
      (node (ref "J00B") (pin "27") (pinfunction "27_27") (pintype "passive"))
    )
    (net (code "71") (name "unconnected-(J00B-Pad28)") (class "Default")
      (node (ref "J00B") (pin "28") (pinfunction "28_28") (pintype "passive"))
    )
    (net (code "72") (name "unconnected-(J01A-PadP1)") (class "Default")
      (node (ref "J01A") (pin "P1") (pinfunction "P1_P1") (pintype "passive+no_connect"))
    )
    (net (code "73") (name "unconnected-(J01A-PadP2)") (class "Default")
      (node (ref "J01A") (pin "P2") (pinfunction "P2_P2") (pintype "passive+no_connect"))
    )
    (net (code "74") (name "unconnected-(J01B-PadP1)") (class "Default")
      (node (ref "J01B") (pin "P1") (pinfunction "P1_P1") (pintype "passive+no_connect"))
    )
    (net (code "75") (name "unconnected-(J01B-PadP2)") (class "Default")
      (node (ref "J01B") (pin "P2") (pinfunction "P2_P2") (pintype "passive+no_connect"))
    )
    (net (code "76") (name "unconnected-(J02A-PadP1)") (class "Default")
      (node (ref "J02A") (pin "P1") (pinfunction "P1_P1") (pintype "passive+no_connect"))
    )
    (net (code "77") (name "unconnected-(J02A-PadP2)") (class "Default")
      (node (ref "J02A") (pin "P2") (pinfunction "P2_P2") (pintype "passive+no_connect"))
    )
    (net (code "78") (name "unconnected-(J02B-PadP1)") (class "Default")
      (node (ref "J02B") (pin "P1") (pinfunction "P1_P1") (pintype "passive+no_connect"))
    )
    (net (code "79") (name "unconnected-(J02B-PadP2)") (class "Default")
      (node (ref "J02B") (pin "P2") (pinfunction "P2_P2") (pintype "passive+no_connect"))
    )
  )
)
